# beacon.net
KiCad netlist of a schematic drawn in EAGLE
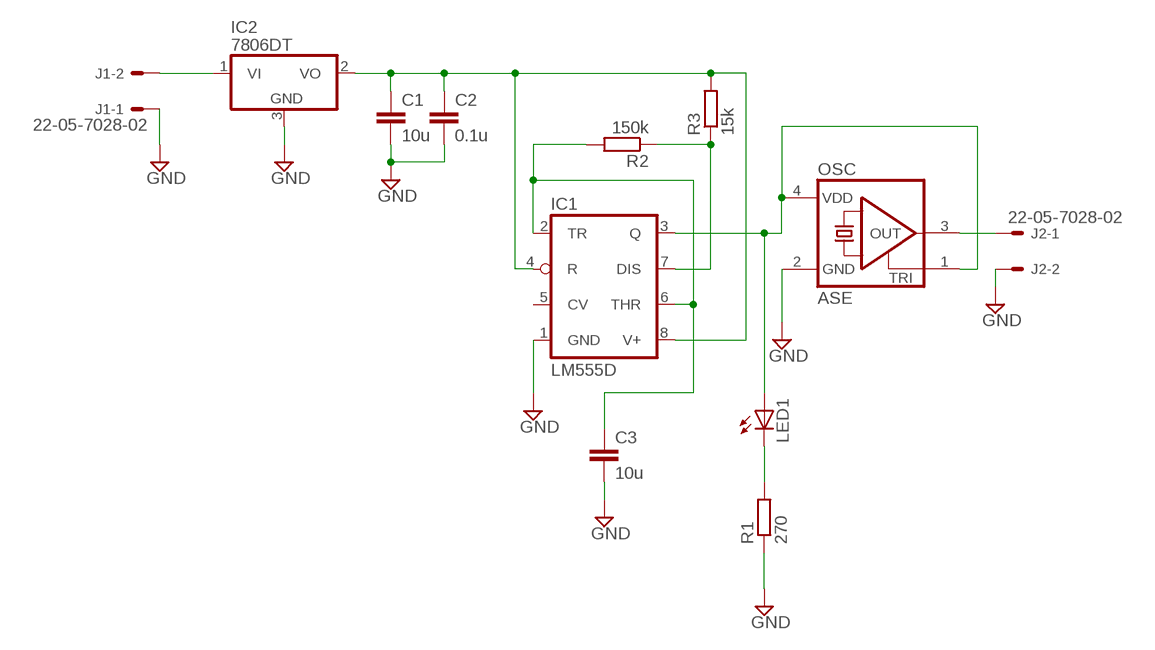
[diagram p0: schematic, sheet 1]

(export (version "E")
  (design (tool "Eeschema 10.0.6"))
  (components
    (comp (ref "C1")
      (value "10u")
      (footprint "eagle-import:C0805")
      (libsource (lib "eagle-import") (part "C"))
    )
    (comp (ref "C2")
      (value "0.1u")
      (footprint "eagle-import:C0805")
      (libsource (lib "eagle-import") (part "C"))
    )
    (comp (ref "C3")
      (value "10u")
      (footprint "eagle-import:C0805")
      (libsource (lib "eagle-import") (part "C"))
    )
    (comp (ref "IC1")
      (value "LM555D")
      (footprint "eagle-import:SO08")
      (libsource (lib "eagle-import") (part "555DLM"))
    )
    (comp (ref "IC2")
      (value "7806DT")
      (footprint "eagle-import:TO252")
      (libsource (lib "eagle-import") (part "78DT06"))
    )
    (comp (ref "J1")
      (value "22-05-7028-02")
      (footprint "eagle-import:7395-02")
      (libsource (lib "eagle-import") (part "22-?-0205-7028"))
    )
    (comp (ref "J2")
      (value "22-05-7028-02")
      (footprint "eagle-import:7395-02")
      (libsource (lib "eagle-import") (part "22-?-0205-7028"))
    )
    (comp (ref "LED1")
      (value "LED5MM")
      (footprint "eagle-import:LED5MM")
      (libsource (lib "eagle-import") (part "LED5MM"))
    )
    (comp (ref "OSC")
      (value "ASE")
      (footprint "eagle-import:ASE")
      (libsource (lib "eagle-import") (part "ASE"))
    )
    (comp (ref "R1")
      (value "270")
      (footprint "eagle-import:R0805")
      (libsource (lib "eagle-import") (part "R"))
    )
    (comp (ref "R2")
      (value "150k")
      (footprint "eagle-import:R0805")
      (libsource (lib "eagle-import") (part "R"))
    )
    (comp (ref "R3")
      (value "15k")
      (footprint "eagle-import:R0805")
      (libsource (lib "eagle-import") (part "R"))
    )
  )
  (nets
    (net (code "1") (name "GND") (class "Default")
      (node (ref "C1") (pin "2") (pinfunction "2_2") (pintype "passive"))
      (node (ref "C2") (pin "2") (pinfunction "2_2") (pintype "passive"))
      (node (ref "C3") (pin "2") (pinfunction "2_2") (pintype "passive"))
      (node (ref "IC1") (pin "1") (pinfunction "GND_1") (pintype "power_in"))
      (node (ref "IC2") (pin "3") (pinfunction "GND_3") (pintype "passive"))
      (node (ref "J1") (pin "1") (pinfunction "S_1") (pintype "passive"))
      (node (ref "J2") (pin "2") (pinfunction "S_2") (pintype "passive"))
      (node (ref "OSC") (pin "2") (pinfunction "GND_2") (pintype "power_in"))
      (node (ref "R1") (pin "1") (pinfunction "1_1") (pintype "passive"))
    )
    (net (code "2") (name "Net-(IC1-DIS)") (class "Default")
      (node (ref "IC1") (pin "7") (pinfunction "DIS_7") (pintype "input"))
      (node (ref "R2") (pin "1") (pinfunction "1_1") (pintype "passive"))
      (node (ref "R3") (pin "1") (pinfunction "1_1") (pintype "passive"))
    )
    (net (code "3") (name "Net-(IC1-Q)") (class "Default")
      (node (ref "IC1") (pin "3") (pinfunction "Q_3") (pintype "output"))
      (node (ref "LED1") (pin "A") (pinfunction "A_A") (pintype "passive"))
      (node (ref "OSC") (pin "1") (pinfunction "TRI_1") (pintype "input"))
      (node (ref "OSC") (pin "4") (pinfunction "VDD_4") (pintype "power_in"))
    )
    (net (code "4") (name "Net-(IC1-R)") (class "Default")
      (node (ref "C1") (pin "1") (pinfunction "1_1") (pintype "passive"))
      (node (ref "C2") (pin "1") (pinfunction "1_1") (pintype "passive"))
      (node (ref "IC1") (pin "4") (pinfunction "R_4") (pintype "input"))
      (node (ref "IC1") (pin "8") (pinfunction "V+_8") (pintype "power_in"))
      (node (ref "IC2") (pin "2") (pinfunction "VO_2") (pintype "passive"))
      (node (ref "R3") (pin "2") (pinfunction "2_2") (pintype "passive"))
    )
    (net (code "5") (name "Net-(IC1-THR)") (class "Default")
      (node (ref "C3") (pin "1") (pinfunction "1_1") (pintype "passive"))
      (node (ref "IC1") (pin "2") (pinfunction "TR_2") (pintype "input"))
      (node (ref "IC1") (pin "6") (pinfunction "THR_6") (pintype "input"))
      (node (ref "R2") (pin "2") (pinfunction "2_2") (pintype "passive"))
    )
    (net (code "6") (name "Net-(IC2-VI)") (class "Default")
      (node (ref "IC2") (pin "1") (pinfunction "VI_1") (pintype "input"))
      (node (ref "J1") (pin "2") (pinfunction "S_2") (pintype "passive"))
    )
    (net (code "7") (name "Net-(J2A-S)") (class "Default")
      (node (ref "J2") (pin "1") (pinfunction "S_1") (pintype "passive"))
      (node (ref "OSC") (pin "3") (pinfunction "OUT_3") (pintype "output"))
    )
    (net (code "8") (name "Net-(LED1-C)") (class "Default")
      (node (ref "LED1") (pin "K") (pinfunction "C_K") (pintype "passive"))
      (node (ref "R1") (pin "2") (pinfunction "2_2") (pintype "passive"))
    )
    (net (code "9") (name "unconnected-(IC1-CV-Pad5)") (class "Default")
      (node (ref "IC1") (pin "5") (pinfunction "CV_5") (pintype "input"))
    )
  )
)
